# L298N_One_Layer.net
KiCad netlist of a schematic drawn in Altium Designer
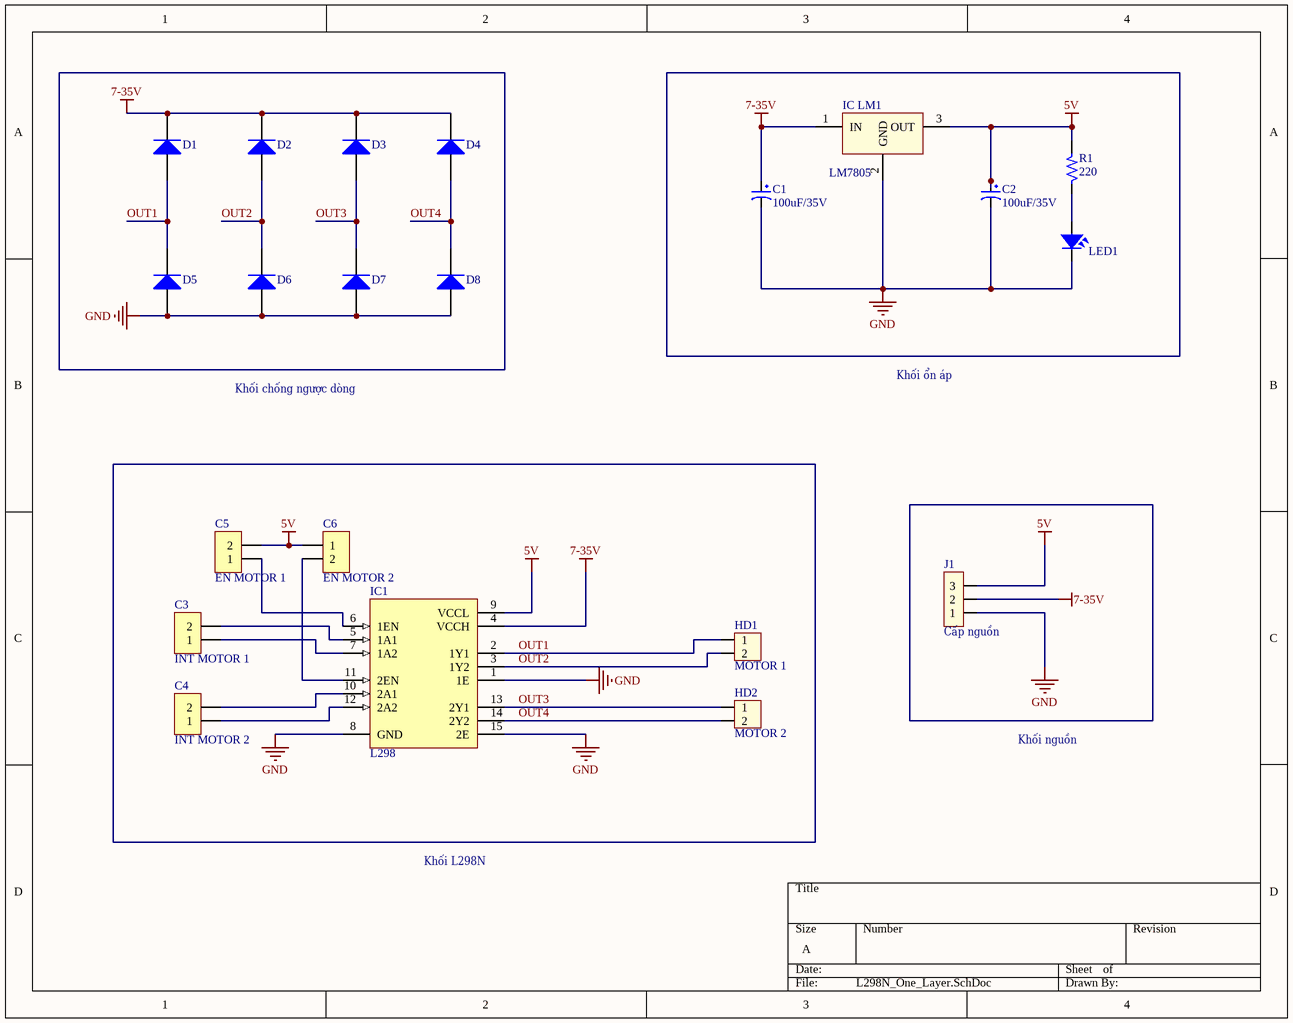
[diagram p0: L298N_One_Layer.SchDoc]

(export (version "E")
  (design (tool "Eeschema 10.0.6"))
  (components
    (comp (ref "C1")
      (value "100uF/35V")
      (footprint "CP1.5/3.4")
      (description "Cap 100uF/35V - 470uF/16V")
      (libsource (lib "echipkool-com-library") (part "CP3"))
    )
    (comp (ref "C2")
      (value "100uF/35V")
      (footprint "CP1.5/3.4")
      (description "Cap 100uF/35V - 470uF/16V")
      (libsource (lib "echipkool-com-library") (part "CP3"))
    )
    (comp (ref "C3")
      (value "INT MOTOR 1")
      (footprint "J2-C1T")
      (description "WR-PHD 2.00 mm Socket Header")
      (fields
        (field (name "MANUFACTURER") "Würth Elektronik eiSos GmbH")
        (field (name "PARTNO") "62000211821")
        (field (name "CREATED BY") "Karrer Zheng")
      )
      (libsource (lib "LIBRARYALT") (part "JP2x1-2.0"))
    )
    (comp (ref "C4")
      (value "INT MOTOR 2")
      (footprint "J2-C1T")
      (description "WR-PHD 2.00 mm Socket Header")
      (fields
        (field (name "MANUFACTURER") "Würth Elektronik eiSos GmbH")
        (field (name "PARTNO") "62000211821")
        (field (name "CREATED BY") "Karrer Zheng")
      )
      (libsource (lib "LIBRARYALT") (part "JP2x1-2.0"))
    )
    (comp (ref "C5")
      (value "EN MOTOR 1")
      (footprint "J2-C1T")
      (description "WR-PHD 2.00 mm Socket Header")
      (fields
        (field (name "MANUFACTURER") "Würth Elektronik eiSos GmbH")
        (field (name "PARTNO") "62000211821")
        (field (name "CREATED BY") "Karrer Zheng")
      )
      (libsource (lib "LIBRARYALT") (part "JP2x1-2.0"))
    )
    (comp (ref "C6")
      (value "EN MOTOR 2")
      (footprint "J2-C1T")
      (description "WR-PHD 2.00 mm Socket Header")
      (fields
        (field (name "MANUFACTURER") "Würth Elektronik eiSos GmbH")
        (field (name "PARTNO") "62000211821")
        (field (name "CREATED BY") "Karrer Zheng")
      )
      (libsource (lib "") (part "JP2x1-2.0_1"))
    )
    (comp (ref "D1")
      (value "Diode")
      (footprint "D5AN")
      (description "Default Diode")
      (fields (field (name "PUBLISHER") "Altium Limited"))
      (libsource (lib "echipkool-com-library") (part "Diode"))
    )
    (comp (ref "D2")
      (value "Diode")
      (footprint "D5AN")
      (description "Default Diode")
      (fields (field (name "PUBLISHER") "Altium Limited"))
      (libsource (lib "echipkool-com-library") (part "Diode"))
    )
    (comp (ref "D3")
      (value "Diode")
      (footprint "D5AN")
      (description "Default Diode")
      (fields (field (name "PUBLISHER") "Altium Limited"))
      (libsource (lib "echipkool-com-library") (part "Diode"))
    )
    (comp (ref "D4")
      (value "Diode")
      (footprint "D5AN")
      (description "Default Diode")
      (fields (field (name "PUBLISHER") "Altium Limited"))
      (libsource (lib "echipkool-com-library") (part "Diode"))
    )
    (comp (ref "D5")
      (value "Diode")
      (footprint "D5AN")
      (description "Default Diode")
      (fields (field (name "PUBLISHER") "Altium Limited"))
      (libsource (lib "echipkool-com-library") (part "Diode"))
    )
    (comp (ref "D6")
      (value "Diode")
      (footprint "D5AN")
      (description "Default Diode")
      (fields (field (name "PUBLISHER") "Altium Limited"))
      (libsource (lib "echipkool-com-library") (part "Diode"))
    )
    (comp (ref "D7")
      (value "Diode")
      (footprint "D5AN")
      (description "Default Diode")
      (fields (field (name "PUBLISHER") "Altium Limited"))
      (libsource (lib "echipkool-com-library") (part "Diode"))
    )
    (comp (ref "D8")
      (value "Diode")
      (footprint "D5AN")
      (description "Default Diode")
      (fields (field (name "PUBLISHER") "Altium Limited"))
      (libsource (lib "echipkool-com-library") (part "Diode"))
    )
    (comp (ref "HD1")
      (value "MOTOR 1")
      (footprint "HED2")
      (description "Header 2 (Green)")
      (libsource (lib "echipkool-com-library") (part "Hed2"))
    )
    (comp (ref "HD2")
      (value "MOTOR 2")
      (footprint "HED2")
      (description "Header 2 (Green)")
      (libsource (lib "echipkool-com-library") (part "Hed2"))
    )
    (comp (ref "IC LM1")
      (value "LM7805")
      (footprint "QTO-220H3")
      (description "On ap +, from + 5 to + 24VDC")
      (libsource (lib "8051_CLOCK") (part "LM78xx"))
    )
    (comp (ref "IC1")
      (value "L298")
      (footprint "DIP15SL2")
      (description "Dual Full-H Driver")
      (fields (field (name "PUBLISHER") "Altium Limited"))
      (libsource (lib "echipkool-com-library") (part "L298"))
    )
    (comp (ref "J1")
      (value "Cấp nguồn")
      (footprint "JP3")
      (description "Jumper 3")
      (libsource (lib "echipkool-com-library") (part "JP3"))
    )
    (comp (ref "LED1")
      (value "LED")
      (footprint "LED-3MM-YELLOW")
      (description "LED Single colour Green and Red")
      (libsource (lib "8051_CLOCK") (part "LED"))
    )
    (comp (ref "R1")
      (value "220")
      (footprint "R1/4W")
      (description "Resistor 1/4W")
      (libsource (lib "8051_CLOCK") (part "Res_1"))
    )
  )
  (nets
    (net (code "1") (name "/OUT1") (class "Default")
      (node (ref "D1") (pin "1") (pinfunction "A_1") (pintype "passive"))
      (node (ref "D5") (pin "2") (pinfunction "K_2") (pintype "passive"))
      (node (ref "HD1") (pin "1") (pinfunction "1_1") (pintype "passive"))
      (node (ref "IC1") (pin "2") (pinfunction "1Y1_2") (pintype "tri_state"))
    )
    (net (code "2") (name "/OUT2") (class "Default")
      (node (ref "D2") (pin "1") (pinfunction "A_1") (pintype "passive"))
      (node (ref "D6") (pin "2") (pinfunction "K_2") (pintype "passive"))
      (node (ref "HD1") (pin "2") (pinfunction "2_2") (pintype "passive"))
      (node (ref "IC1") (pin "3") (pinfunction "1Y2_3") (pintype "tri_state"))
    )
    (net (code "3") (name "/OUT3") (class "Default")
      (node (ref "D3") (pin "1") (pinfunction "A_1") (pintype "passive"))
      (node (ref "D7") (pin "2") (pinfunction "K_2") (pintype "passive"))
      (node (ref "HD2") (pin "1") (pinfunction "1_1") (pintype "passive"))
      (node (ref "IC1") (pin "13") (pinfunction "2Y1_13") (pintype "tri_state"))
    )
    (net (code "4") (name "/OUT4") (class "Default")
      (node (ref "D4") (pin "1") (pinfunction "A_1") (pintype "passive"))
      (node (ref "D8") (pin "2") (pinfunction "K_2") (pintype "passive"))
      (node (ref "HD2") (pin "2") (pinfunction "2_2") (pintype "passive"))
      (node (ref "IC1") (pin "14") (pinfunction "2Y2_14") (pintype "tri_state"))
    )
    (net (code "5") (name "5V") (class "Default")
      (node (ref "C2") (pin "1") (pinfunction "1_1") (pintype "passive"))
      (node (ref "C5") (pin "2") (pinfunction "2_2") (pintype "passive"))
      (node (ref "C6") (pin "1") (pinfunction "1_1") (pintype "passive"))
      (node (ref "IC LM1") (pin "3") (pinfunction "OUT_3") (pintype "passive"))
      (node (ref "IC1") (pin "9") (pinfunction "VCCL_9") (pintype "power_in"))
      (node (ref "J1") (pin "3") (pinfunction "3_3") (pintype "passive"))
      (node (ref "R1") (pin "2") (pinfunction "2_2") (pintype "passive"))
    )
    (net (code "6") (name "7-35V") (class "Default")
      (node (ref "C1") (pin "1") (pinfunction "1_1") (pintype "passive"))
      (node (ref "D1") (pin "2") (pinfunction "K_2") (pintype "passive"))
      (node (ref "D2") (pin "2") (pinfunction "K_2") (pintype "passive"))
      (node (ref "D3") (pin "2") (pinfunction "K_2") (pintype "passive"))
      (node (ref "D4") (pin "2") (pinfunction "K_2") (pintype "passive"))
      (node (ref "IC LM1") (pin "1") (pinfunction "IN_1") (pintype "passive"))
      (node (ref "IC1") (pin "4") (pinfunction "VCCH_4") (pintype "power_in"))
      (node (ref "J1") (pin "2") (pinfunction "2_2") (pintype "passive"))
    )
    (net (code "7") (name "GND") (class "Default")
      (node (ref "C1") (pin "2") (pinfunction "2_2") (pintype "passive"))
      (node (ref "C2") (pin "2") (pinfunction "2_2") (pintype "passive"))
      (node (ref "D5") (pin "1") (pinfunction "A_1") (pintype "passive"))
      (node (ref "D6") (pin "1") (pinfunction "A_1") (pintype "passive"))
      (node (ref "D7") (pin "1") (pinfunction "A_1") (pintype "passive"))
      (node (ref "D8") (pin "1") (pinfunction "A_1") (pintype "passive"))
      (node (ref "IC LM1") (pin "2") (pinfunction "GND_2") (pintype "passive"))
      (node (ref "IC1") (pin "1") (pinfunction "1E_1") (pintype "passive"))
      (node (ref "IC1") (pin "15") (pinfunction "2E_15") (pintype "passive"))
      (node (ref "IC1") (pin "8") (pinfunction "GND_8") (pintype "power_in"))
      (node (ref "J1") (pin "1") (pinfunction "1_1") (pintype "passive"))
      (node (ref "LED1") (pin "2") (pinfunction "2_2") (pintype "passive"))
    )
    (net (code "8") (name "Net-(IC1-1A1)") (class "Default")
      (node (ref "C3") (pin "2") (pinfunction "2_2") (pintype "passive"))
      (node (ref "IC1") (pin "5") (pinfunction "1A1_5") (pintype "input"))
    )
    (net (code "9") (name "Net-(IC1-1A2)") (class "Default")
      (node (ref "C3") (pin "1") (pinfunction "1_1") (pintype "passive"))
      (node (ref "IC1") (pin "7") (pinfunction "1A2_7") (pintype "input"))
    )
    (net (code "10") (name "Net-(IC1-1EN)") (class "Default")
      (node (ref "C5") (pin "1") (pinfunction "1_1") (pintype "passive"))
      (node (ref "IC1") (pin "6") (pinfunction "1EN_6") (pintype "input"))
    )
    (net (code "11") (name "Net-(IC1-2A1)") (class "Default")
      (node (ref "C4") (pin "2") (pinfunction "2_2") (pintype "passive"))
      (node (ref "IC1") (pin "10") (pinfunction "2A1_10") (pintype "input"))
    )
    (net (code "12") (name "Net-(IC1-2A2)") (class "Default")
      (node (ref "C4") (pin "1") (pinfunction "1_1") (pintype "passive"))
      (node (ref "IC1") (pin "12") (pinfunction "2A2_12") (pintype "input"))
    )
    (net (code "13") (name "Net-(IC1-2EN)") (class "Default")
      (node (ref "C6") (pin "2") (pinfunction "2_2") (pintype "passive"))
      (node (ref "IC1") (pin "11") (pinfunction "2EN_11") (pintype "input"))
    )
    (net (code "14") (name "Net-(LED1-Pad1)") (class "Default")
      (node (ref "LED1") (pin "1") (pinfunction "1_1") (pintype "passive"))
      (node (ref "R1") (pin "1") (pinfunction "1_1") (pintype "passive"))
    )
  )
)
